# 2020-03-07_LN2_Autofill_Connectors_-_Cop.net
KiCad netlist of a schematic drawn in EAGLE
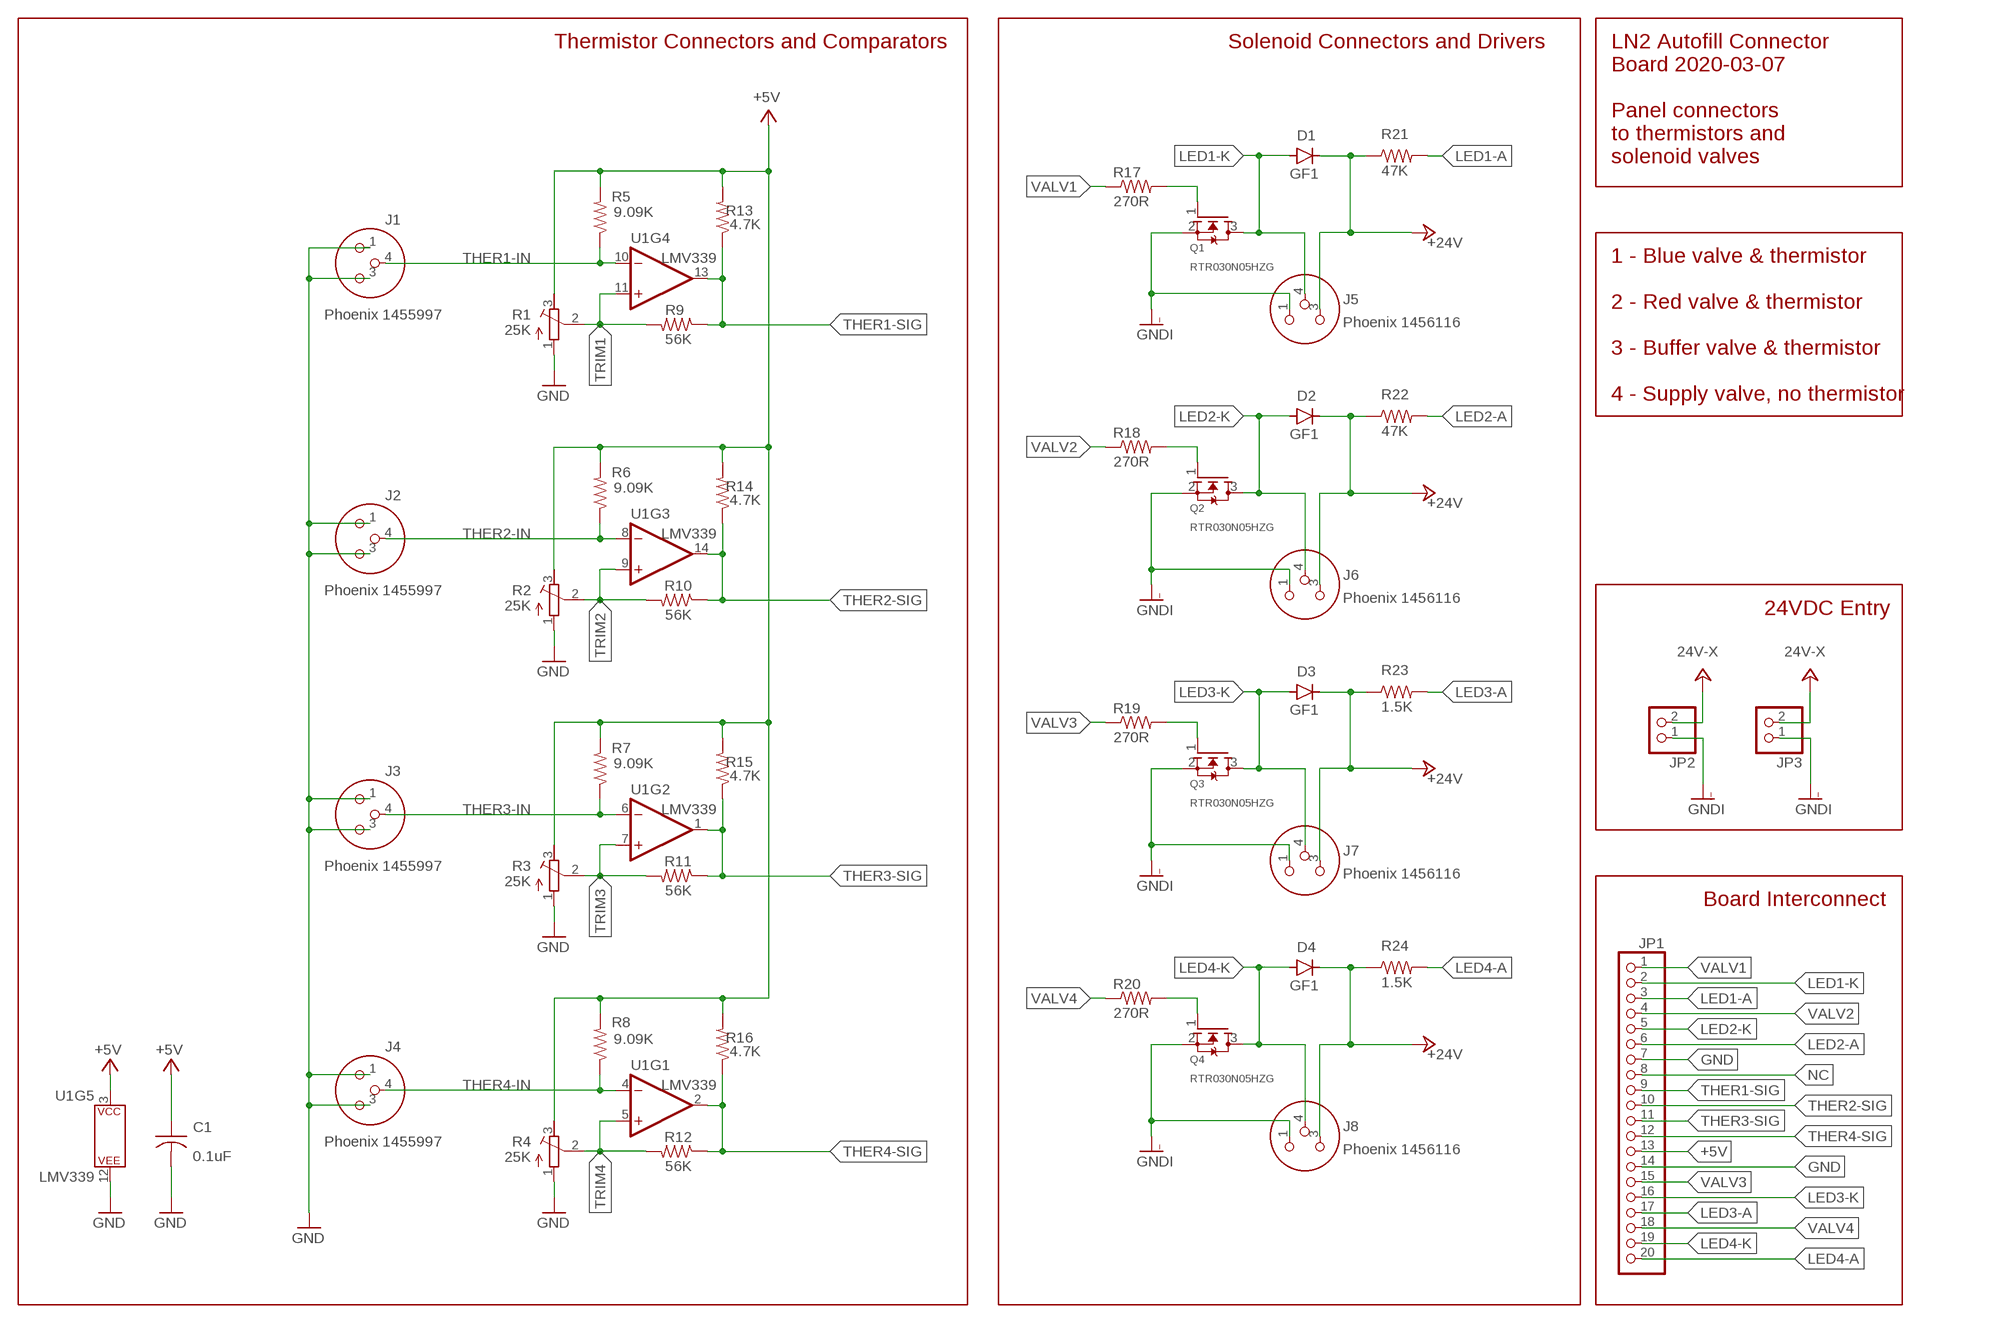
[diagram p0: schematic, sheet 1]

(export (version "E")
  (design (tool "Eeschema 10.0.6"))
  (components
    (comp (ref "C1")
      (value "0.1uF")
      (footprint "eagle-import:C0805")
      (libsource (lib "eagle-import") (part "C-USC0805"))
    )
    (comp (ref "D1")
      (value "GF1")
      (footprint "eagle-import:SMA-DO214AC")
      (libsource (lib "eagle-import") (part "GF1"))
    )
    (comp (ref "D2")
      (value "GF1")
      (footprint "eagle-import:SMA-DO214AC")
      (libsource (lib "eagle-import") (part "GF1"))
    )
    (comp (ref "D3")
      (value "GF1")
      (footprint "eagle-import:SMA-DO214AC")
      (libsource (lib "eagle-import") (part "GF1"))
    )
    (comp (ref "D4")
      (value "GF1")
      (footprint "eagle-import:SMA-DO214AC")
      (libsource (lib "eagle-import") (part "GF1"))
    )
    (comp (ref "J1")
      (value "Phoenix 1455997")
      (footprint "eagle-import:PHOENIX-3PIN")
      (libsource (lib "eagle-import") (part "PHOENIX-3PIN-MALE"))
    )
    (comp (ref "J2")
      (value "Phoenix 1455997")
      (footprint "eagle-import:PHOENIX-3PIN")
      (libsource (lib "eagle-import") (part "PHOENIX-3PIN-MALE"))
    )
    (comp (ref "J3")
      (value "Phoenix 1455997")
      (footprint "eagle-import:PHOENIX-3PIN")
      (libsource (lib "eagle-import") (part "PHOENIX-3PIN-MALE"))
    )
    (comp (ref "J4")
      (value "Phoenix 1455997")
      (footprint "eagle-import:PHOENIX-3PIN")
      (libsource (lib "eagle-import") (part "PHOENIX-3PIN-MALE"))
    )
    (comp (ref "J5")
      (value "Phoenix 1456116")
      (footprint "eagle-import:PHOENIX-3PIN-FEMALE")
      (libsource (lib "eagle-import") (part "PHOENIX-3PIN-FEMALE"))
    )
    (comp (ref "J6")
      (value "Phoenix 1456116")
      (footprint "eagle-import:PHOENIX-3PIN-FEMALE")
      (libsource (lib "eagle-import") (part "PHOENIX-3PIN-FEMALE"))
    )
    (comp (ref "J7")
      (value "Phoenix 1456116")
      (footprint "eagle-import:PHOENIX-3PIN-FEMALE")
      (libsource (lib "eagle-import") (part "PHOENIX-3PIN-FEMALE"))
    )
    (comp (ref "J8")
      (value "Phoenix 1456116")
      (footprint "eagle-import:PHOENIX-3PIN-FEMALE")
      (libsource (lib "eagle-import") (part "PHOENIX-3PIN-FEMALE"))
    )
    (comp (ref "JP1")
      (value "PINHD-1X20")
      (footprint "eagle-import:1X20")
      (libsource (lib "eagle-import") (part "PINHD-1X20"))
    )
    (comp (ref "JP2")
      (value "PINHD-1X2MOLEX-02-VERT")
      (footprint "eagle-import:MOLEX-02-VERT")
      (libsource (lib "eagle-import") (part "PINHD-1X2MOLEX-02-VERT"))
    )
    (comp (ref "JP3")
      (value "PINHD-1X2MOLEX-02-VERT")
      (footprint "eagle-import:MOLEX-02-VERT")
      (libsource (lib "eagle-import") (part "PINHD-1X2MOLEX-02-VERT"))
    )
    (comp (ref "Q1")
      (value "RTR030N05HZG")
      (footprint "eagle-import:SOT23")
      (libsource (lib "eagle-import") (part "MOSFET-NREFLOW"))
    )
    (comp (ref "Q2")
      (value "RTR030N05HZG")
      (footprint "eagle-import:SOT23")
      (libsource (lib "eagle-import") (part "MOSFET-NREFLOW"))
    )
    (comp (ref "Q3")
      (value "RTR030N05HZG")
      (footprint "eagle-import:SOT23")
      (libsource (lib "eagle-import") (part "MOSFET-NREFLOW"))
    )
    (comp (ref "Q4")
      (value "RTR030N05HZG")
      (footprint "eagle-import:SOT23")
      (libsource (lib "eagle-import") (part "MOSFET-NREFLOW"))
    )
    (comp (ref "R1")
      (value "25K")
      (footprint "eagle-import:RTRIM3296Y")
      (libsource (lib "eagle-import") (part "R-TRIMM3296Y"))
    )
    (comp (ref "R2")
      (value "25K")
      (footprint "eagle-import:RTRIM3296Y")
      (libsource (lib "eagle-import") (part "R-TRIMM3296Y"))
    )
    (comp (ref "R3")
      (value "25K")
      (footprint "eagle-import:RTRIM3296Y")
      (libsource (lib "eagle-import") (part "R-TRIMM3296Y"))
    )
    (comp (ref "R4")
      (value "25K")
      (footprint "eagle-import:RTRIM3296Y")
      (libsource (lib "eagle-import") (part "R-TRIMM3296Y"))
    )
    (comp (ref "R5")
      (value "9.09K")
      (footprint "eagle-import:R0805")
      (libsource (lib "eagle-import") (part "R-US_R0805"))
    )
    (comp (ref "R6")
      (value "9.09K")
      (footprint "eagle-import:R0805")
      (libsource (lib "eagle-import") (part "R-US_R0805"))
    )
    (comp (ref "R7")
      (value "9.09K")
      (footprint "eagle-import:R0805")
      (libsource (lib "eagle-import") (part "R-US_R0805"))
    )
    (comp (ref "R8")
      (value "9.09K")
      (footprint "eagle-import:R0805")
      (libsource (lib "eagle-import") (part "R-US_R0805"))
    )
    (comp (ref "R9")
      (value "56K")
      (footprint "eagle-import:R0805")
      (libsource (lib "eagle-import") (part "R-US_R0805"))
    )
    (comp (ref "R10")
      (value "56K")
      (footprint "eagle-import:R0805")
      (libsource (lib "eagle-import") (part "R-US_R0805"))
    )
    (comp (ref "R11")
      (value "56K")
      (footprint "eagle-import:R0805")
      (libsource (lib "eagle-import") (part "R-US_R0805"))
    )
    (comp (ref "R12")
      (value "56K")
      (footprint "eagle-import:R0805")
      (libsource (lib "eagle-import") (part "R-US_R0805"))
    )
    (comp (ref "R13")
      (value "4.7K")
      (footprint "eagle-import:R0805")
      (libsource (lib "eagle-import") (part "R-US_R0805"))
    )
    (comp (ref "R14")
      (value "4.7K")
      (footprint "eagle-import:R0805")
      (libsource (lib "eagle-import") (part "R-US_R0805"))
    )
    (comp (ref "R15")
      (value "4.7K")
      (footprint "eagle-import:R0805")
      (libsource (lib "eagle-import") (part "R-US_R0805"))
    )
    (comp (ref "R16")
      (value "4.7K")
      (footprint "eagle-import:R0805")
      (libsource (lib "eagle-import") (part "R-US_R0805"))
    )
    (comp (ref "R17")
      (value "270R")
      (footprint "eagle-import:R0805")
      (libsource (lib "eagle-import") (part "R-US_R0805"))
    )
    (comp (ref "R18")
      (value "270R")
      (footprint "eagle-import:R0805")
      (libsource (lib "eagle-import") (part "R-US_R0805"))
    )
    (comp (ref "R19")
      (value "270R")
      (footprint "eagle-import:R0805")
      (libsource (lib "eagle-import") (part "R-US_R0805"))
    )
    (comp (ref "R20")
      (value "270R")
      (footprint "eagle-import:R0805")
      (libsource (lib "eagle-import") (part "R-US_R0805"))
    )
    (comp (ref "R21")
      (value "47K")
      (footprint "eagle-import:R0805")
      (libsource (lib "eagle-import") (part "R-US_R0805"))
    )
    (comp (ref "R22")
      (value "47K")
      (footprint "eagle-import:R0805")
      (libsource (lib "eagle-import") (part "R-US_R0805"))
    )
    (comp (ref "R23")
      (value "1.5K")
      (footprint "eagle-import:R0805")
      (libsource (lib "eagle-import") (part "R-US_R0805"))
    )
    (comp (ref "R24")
      (value "1.5K")
      (footprint "eagle-import:R0805")
      (libsource (lib "eagle-import") (part "R-US_R0805"))
    )
    (comp (ref "U1")
      (value "LMV339")
      (footprint "eagle-import:SOIC127P599X175-14")
      (libsource (lib "eagle-import") (part "LM339SOIC-14"))
    )
  )
  (nets
    (net (code "1") (name "+5V") (class "Default")
      (node (ref "C1") (pin "1") (pinfunction "1_1") (pintype "passive"))
      (node (ref "JP1") (pin "13") (pinfunction "13_13") (pintype "passive"))
      (node (ref "R1") (pin "3") (pinfunction "E_3") (pintype "passive"))
      (node (ref "R13") (pin "2") (pinfunction "2_2") (pintype "passive"))
      (node (ref "R14") (pin "2") (pinfunction "2_2") (pintype "passive"))
      (node (ref "R15") (pin "2") (pinfunction "2_2") (pintype "passive"))
      (node (ref "R16") (pin "2") (pinfunction "2_2") (pintype "passive"))
      (node (ref "R2") (pin "3") (pinfunction "E_3") (pintype "passive"))
      (node (ref "R3") (pin "3") (pinfunction "E_3") (pintype "passive"))
      (node (ref "R4") (pin "3") (pinfunction "E_3") (pintype "passive"))
      (node (ref "R5") (pin "2") (pinfunction "2_2") (pintype "passive"))
      (node (ref "R6") (pin "2") (pinfunction "2_2") (pintype "passive"))
      (node (ref "R7") (pin "2") (pinfunction "2_2") (pintype "passive"))
      (node (ref "R8") (pin "2") (pinfunction "2_2") (pintype "passive"))
      (node (ref "U1") (pin "3") (pinfunction "P$V+_3") (pintype "bidirectional"))
    )
    (net (code "2") (name "+24V") (class "Default")
      (node (ref "D1") (pin "K") (pinfunction "C_K") (pintype "passive"))
      (node (ref "D2") (pin "K") (pinfunction "C_K") (pintype "passive"))
      (node (ref "D3") (pin "K") (pinfunction "C_K") (pintype "passive"))
      (node (ref "D4") (pin "K") (pinfunction "C_K") (pintype "passive"))
      (node (ref "J5") (pin "3") (pinfunction "3_3") (pintype "passive"))
      (node (ref "J6") (pin "3") (pinfunction "3_3") (pintype "passive"))
      (node (ref "J7") (pin "3") (pinfunction "3_3") (pintype "passive"))
      (node (ref "J8") (pin "3") (pinfunction "3_3") (pintype "passive"))
      (node (ref "JP2") (pin "2") (pinfunction "2_2") (pintype "passive"))
      (node (ref "JP3") (pin "2") (pinfunction "2_2") (pintype "passive"))
      (node (ref "R21") (pin "1") (pinfunction "1_1") (pintype "passive"))
      (node (ref "R22") (pin "1") (pinfunction "1_1") (pintype "passive"))
      (node (ref "R23") (pin "1") (pinfunction "1_1") (pintype "passive"))
      (node (ref "R24") (pin "1") (pinfunction "1_1") (pintype "passive"))
    )
    (net (code "3") (name "/THER1-IN") (class "Default")
      (node (ref "J1") (pin "4") (pinfunction "4_4") (pintype "passive"))
      (node (ref "R5") (pin "1") (pinfunction "1_1") (pintype "passive"))
      (node (ref "U1") (pin "10") (pinfunction "-IN_10") (pintype "input"))
    )
    (net (code "4") (name "/THER2-IN") (class "Default")
      (node (ref "J2") (pin "4") (pinfunction "4_4") (pintype "passive"))
      (node (ref "R6") (pin "1") (pinfunction "1_1") (pintype "passive"))
      (node (ref "U1") (pin "8") (pinfunction "-IN_8") (pintype "input"))
    )
    (net (code "5") (name "/THER3-IN") (class "Default")
      (node (ref "J3") (pin "4") (pinfunction "4_4") (pintype "passive"))
      (node (ref "R7") (pin "1") (pinfunction "1_1") (pintype "passive"))
      (node (ref "U1") (pin "6") (pinfunction "-IN_6") (pintype "input"))
    )
    (net (code "6") (name "/THER4-IN") (class "Default")
      (node (ref "J4") (pin "4") (pinfunction "4_4") (pintype "passive"))
      (node (ref "R8") (pin "1") (pinfunction "1_1") (pintype "passive"))
      (node (ref "U1") (pin "4") (pinfunction "-IN_4") (pintype "input"))
    )
    (net (code "7") (name "GND") (class "Default")
      (node (ref "C1") (pin "2") (pinfunction "2_2") (pintype "passive"))
      (node (ref "J1") (pin "1") (pinfunction "1_1") (pintype "passive"))
      (node (ref "J1") (pin "3") (pinfunction "3_3") (pintype "passive"))
      (node (ref "J2") (pin "1") (pinfunction "1_1") (pintype "passive"))
      (node (ref "J2") (pin "3") (pinfunction "3_3") (pintype "passive"))
      (node (ref "J3") (pin "1") (pinfunction "1_1") (pintype "passive"))
      (node (ref "J3") (pin "3") (pinfunction "3_3") (pintype "passive"))
      (node (ref "J4") (pin "1") (pinfunction "1_1") (pintype "passive"))
      (node (ref "J4") (pin "3") (pinfunction "3_3") (pintype "passive"))
      (node (ref "JP1") (pin "14") (pinfunction "14_14") (pintype "passive"))
      (node (ref "JP1") (pin "7") (pinfunction "7_7") (pintype "passive"))
      (node (ref "R1") (pin "1") (pinfunction "A_1") (pintype "passive"))
      (node (ref "R2") (pin "1") (pinfunction "A_1") (pintype "passive"))
      (node (ref "R3") (pin "1") (pinfunction "A_1") (pintype "passive"))
      (node (ref "R4") (pin "1") (pinfunction "A_1") (pintype "passive"))
      (node (ref "U1") (pin "12") (pinfunction "P$V-_12") (pintype "bidirectional"))
    )
    (net (code "8") (name "GNDI") (class "Default")
      (node (ref "J5") (pin "1") (pinfunction "1_1") (pintype "passive"))
      (node (ref "J6") (pin "1") (pinfunction "1_1") (pintype "passive"))
      (node (ref "J7") (pin "1") (pinfunction "1_1") (pintype "passive"))
      (node (ref "J8") (pin "1") (pinfunction "1_1") (pintype "passive"))
      (node (ref "JP2") (pin "1") (pinfunction "1_1") (pintype "passive"))
      (node (ref "JP3") (pin "1") (pinfunction "1_1") (pintype "passive"))
      (node (ref "Q1") (pin "2") (pinfunction "S_2") (pintype "bidirectional"))
      (node (ref "Q2") (pin "2") (pinfunction "S_2") (pintype "bidirectional"))
      (node (ref "Q3") (pin "2") (pinfunction "S_2") (pintype "bidirectional"))
      (node (ref "Q4") (pin "2") (pinfunction "S_2") (pintype "bidirectional"))
    )
    (net (code "9") (name "LED1-A") (class "Default")
      (node (ref "JP1") (pin "3") (pinfunction "3_3") (pintype "passive"))
      (node (ref "R21") (pin "2") (pinfunction "2_2") (pintype "passive"))
    )
    (net (code "10") (name "LED1-K") (class "Default")
      (node (ref "D1") (pin "A") (pinfunction "A_A") (pintype "passive"))
      (node (ref "J5") (pin "4") (pinfunction "4_4") (pintype "passive"))
      (node (ref "JP1") (pin "2") (pinfunction "2_2") (pintype "passive"))
      (node (ref "Q1") (pin "3") (pinfunction "D_3") (pintype "bidirectional"))
    )
    (net (code "11") (name "LED2-A") (class "Default")
      (node (ref "JP1") (pin "6") (pinfunction "6_6") (pintype "passive"))
      (node (ref "R22") (pin "2") (pinfunction "2_2") (pintype "passive"))
    )
    (net (code "12") (name "LED2-K") (class "Default")
      (node (ref "D2") (pin "A") (pinfunction "A_A") (pintype "passive"))
      (node (ref "J6") (pin "4") (pinfunction "4_4") (pintype "passive"))
      (node (ref "JP1") (pin "5") (pinfunction "5_5") (pintype "passive"))
      (node (ref "Q2") (pin "3") (pinfunction "D_3") (pintype "bidirectional"))
    )
    (net (code "13") (name "LED3-A") (class "Default")
      (node (ref "JP1") (pin "17") (pinfunction "17_17") (pintype "passive"))
      (node (ref "R23") (pin "2") (pinfunction "2_2") (pintype "passive"))
    )
    (net (code "14") (name "LED3-K") (class "Default")
      (node (ref "D3") (pin "A") (pinfunction "A_A") (pintype "passive"))
      (node (ref "J7") (pin "4") (pinfunction "4_4") (pintype "passive"))
      (node (ref "JP1") (pin "16") (pinfunction "16_16") (pintype "passive"))
      (node (ref "Q3") (pin "3") (pinfunction "D_3") (pintype "bidirectional"))
    )
    (net (code "15") (name "LED4-A") (class "Default")
      (node (ref "JP1") (pin "20") (pinfunction "20_20") (pintype "passive"))
      (node (ref "R24") (pin "2") (pinfunction "2_2") (pintype "passive"))
    )
    (net (code "16") (name "LED4-K") (class "Default")
      (node (ref "D4") (pin "A") (pinfunction "A_A") (pintype "passive"))
      (node (ref "J8") (pin "4") (pinfunction "4_4") (pintype "passive"))
      (node (ref "JP1") (pin "19") (pinfunction "19_19") (pintype "passive"))
      (node (ref "Q4") (pin "3") (pinfunction "D_3") (pintype "bidirectional"))
    )
    (net (code "17") (name "NC") (class "Default")
      (node (ref "JP1") (pin "8") (pinfunction "8_8") (pintype "passive"))
    )
    (net (code "18") (name "Net-(Q1-G)") (class "Default")
      (node (ref "Q1") (pin "1") (pinfunction "G_1") (pintype "bidirectional"))
      (node (ref "R17") (pin "2") (pinfunction "2_2") (pintype "passive"))
    )
    (net (code "19") (name "Net-(Q2-G)") (class "Default")
      (node (ref "Q2") (pin "1") (pinfunction "G_1") (pintype "bidirectional"))
      (node (ref "R18") (pin "2") (pinfunction "2_2") (pintype "passive"))
    )
    (net (code "20") (name "Net-(Q3-G)") (class "Default")
      (node (ref "Q3") (pin "1") (pinfunction "G_1") (pintype "bidirectional"))
      (node (ref "R19") (pin "2") (pinfunction "2_2") (pintype "passive"))
    )
    (net (code "21") (name "Net-(Q4-G)") (class "Default")
      (node (ref "Q4") (pin "1") (pinfunction "G_1") (pintype "bidirectional"))
      (node (ref "R20") (pin "2") (pinfunction "2_2") (pintype "passive"))
    )
    (net (code "22") (name "THER1-SIG") (class "Default")
      (node (ref "JP1") (pin "9") (pinfunction "9_9") (pintype "passive"))
      (node (ref "R13") (pin "1") (pinfunction "1_1") (pintype "passive"))
      (node (ref "R9") (pin "1") (pinfunction "1_1") (pintype "passive"))
      (node (ref "U1") (pin "13") (pinfunction "OUT_13") (pintype "output"))
    )
    (net (code "23") (name "THER2-SIG") (class "Default")
      (node (ref "JP1") (pin "10") (pinfunction "10_10") (pintype "passive"))
      (node (ref "R10") (pin "1") (pinfunction "1_1") (pintype "passive"))
      (node (ref "R14") (pin "1") (pinfunction "1_1") (pintype "passive"))
      (node (ref "U1") (pin "14") (pinfunction "OUT_14") (pintype "output"))
    )
    (net (code "24") (name "THER3-SIG") (class "Default")
      (node (ref "JP1") (pin "11") (pinfunction "11_11") (pintype "passive"))
      (node (ref "R11") (pin "1") (pinfunction "1_1") (pintype "passive"))
      (node (ref "R15") (pin "1") (pinfunction "1_1") (pintype "passive"))
      (node (ref "U1") (pin "1") (pinfunction "OUT_1") (pintype "output"))
    )
    (net (code "25") (name "THER4-SIG") (class "Default")
      (node (ref "JP1") (pin "12") (pinfunction "12_12") (pintype "passive"))
      (node (ref "R12") (pin "1") (pinfunction "1_1") (pintype "passive"))
      (node (ref "R16") (pin "1") (pinfunction "1_1") (pintype "passive"))
      (node (ref "U1") (pin "2") (pinfunction "OUT_2") (pintype "output"))
    )
    (net (code "26") (name "TRIM1") (class "Default")
      (node (ref "R1") (pin "2") (pinfunction "S_2") (pintype "passive"))
      (node (ref "R9") (pin "2") (pinfunction "2_2") (pintype "passive"))
      (node (ref "U1") (pin "11") (pinfunction "+IN_11") (pintype "input"))
    )
    (net (code "27") (name "TRIM2") (class "Default")
      (node (ref "R10") (pin "2") (pinfunction "2_2") (pintype "passive"))
      (node (ref "R2") (pin "2") (pinfunction "S_2") (pintype "passive"))
      (node (ref "U1") (pin "9") (pinfunction "+IN_9") (pintype "input"))
    )
    (net (code "28") (name "TRIM3") (class "Default")
      (node (ref "R11") (pin "2") (pinfunction "2_2") (pintype "passive"))
      (node (ref "R3") (pin "2") (pinfunction "S_2") (pintype "passive"))
      (node (ref "U1") (pin "7") (pinfunction "+IN_7") (pintype "input"))
    )
    (net (code "29") (name "TRIM4") (class "Default")
      (node (ref "R12") (pin "2") (pinfunction "2_2") (pintype "passive"))
      (node (ref "R4") (pin "2") (pinfunction "S_2") (pintype "passive"))
      (node (ref "U1") (pin "5") (pinfunction "+IN_5") (pintype "input"))
    )
    (net (code "30") (name "VALV1") (class "Default")
      (node (ref "JP1") (pin "1") (pinfunction "1_1") (pintype "passive"))
      (node (ref "R17") (pin "1") (pinfunction "1_1") (pintype "passive"))
    )
    (net (code "31") (name "VALV2") (class "Default")
      (node (ref "JP1") (pin "4") (pinfunction "4_4") (pintype "passive"))
      (node (ref "R18") (pin "1") (pinfunction "1_1") (pintype "passive"))
    )
    (net (code "32") (name "VALV3") (class "Default")
      (node (ref "JP1") (pin "15") (pinfunction "15_15") (pintype "passive"))
      (node (ref "R19") (pin "1") (pinfunction "1_1") (pintype "passive"))
    )
    (net (code "33") (name "VALV4") (class "Default")
      (node (ref "JP1") (pin "18") (pinfunction "18_18") (pintype "passive"))
      (node (ref "R20") (pin "1") (pinfunction "1_1") (pintype "passive"))
    )
  )
)
